# ItsyBitsy_Expander_v1_0.net
KiCad netlist of a schematic drawn in EAGLE
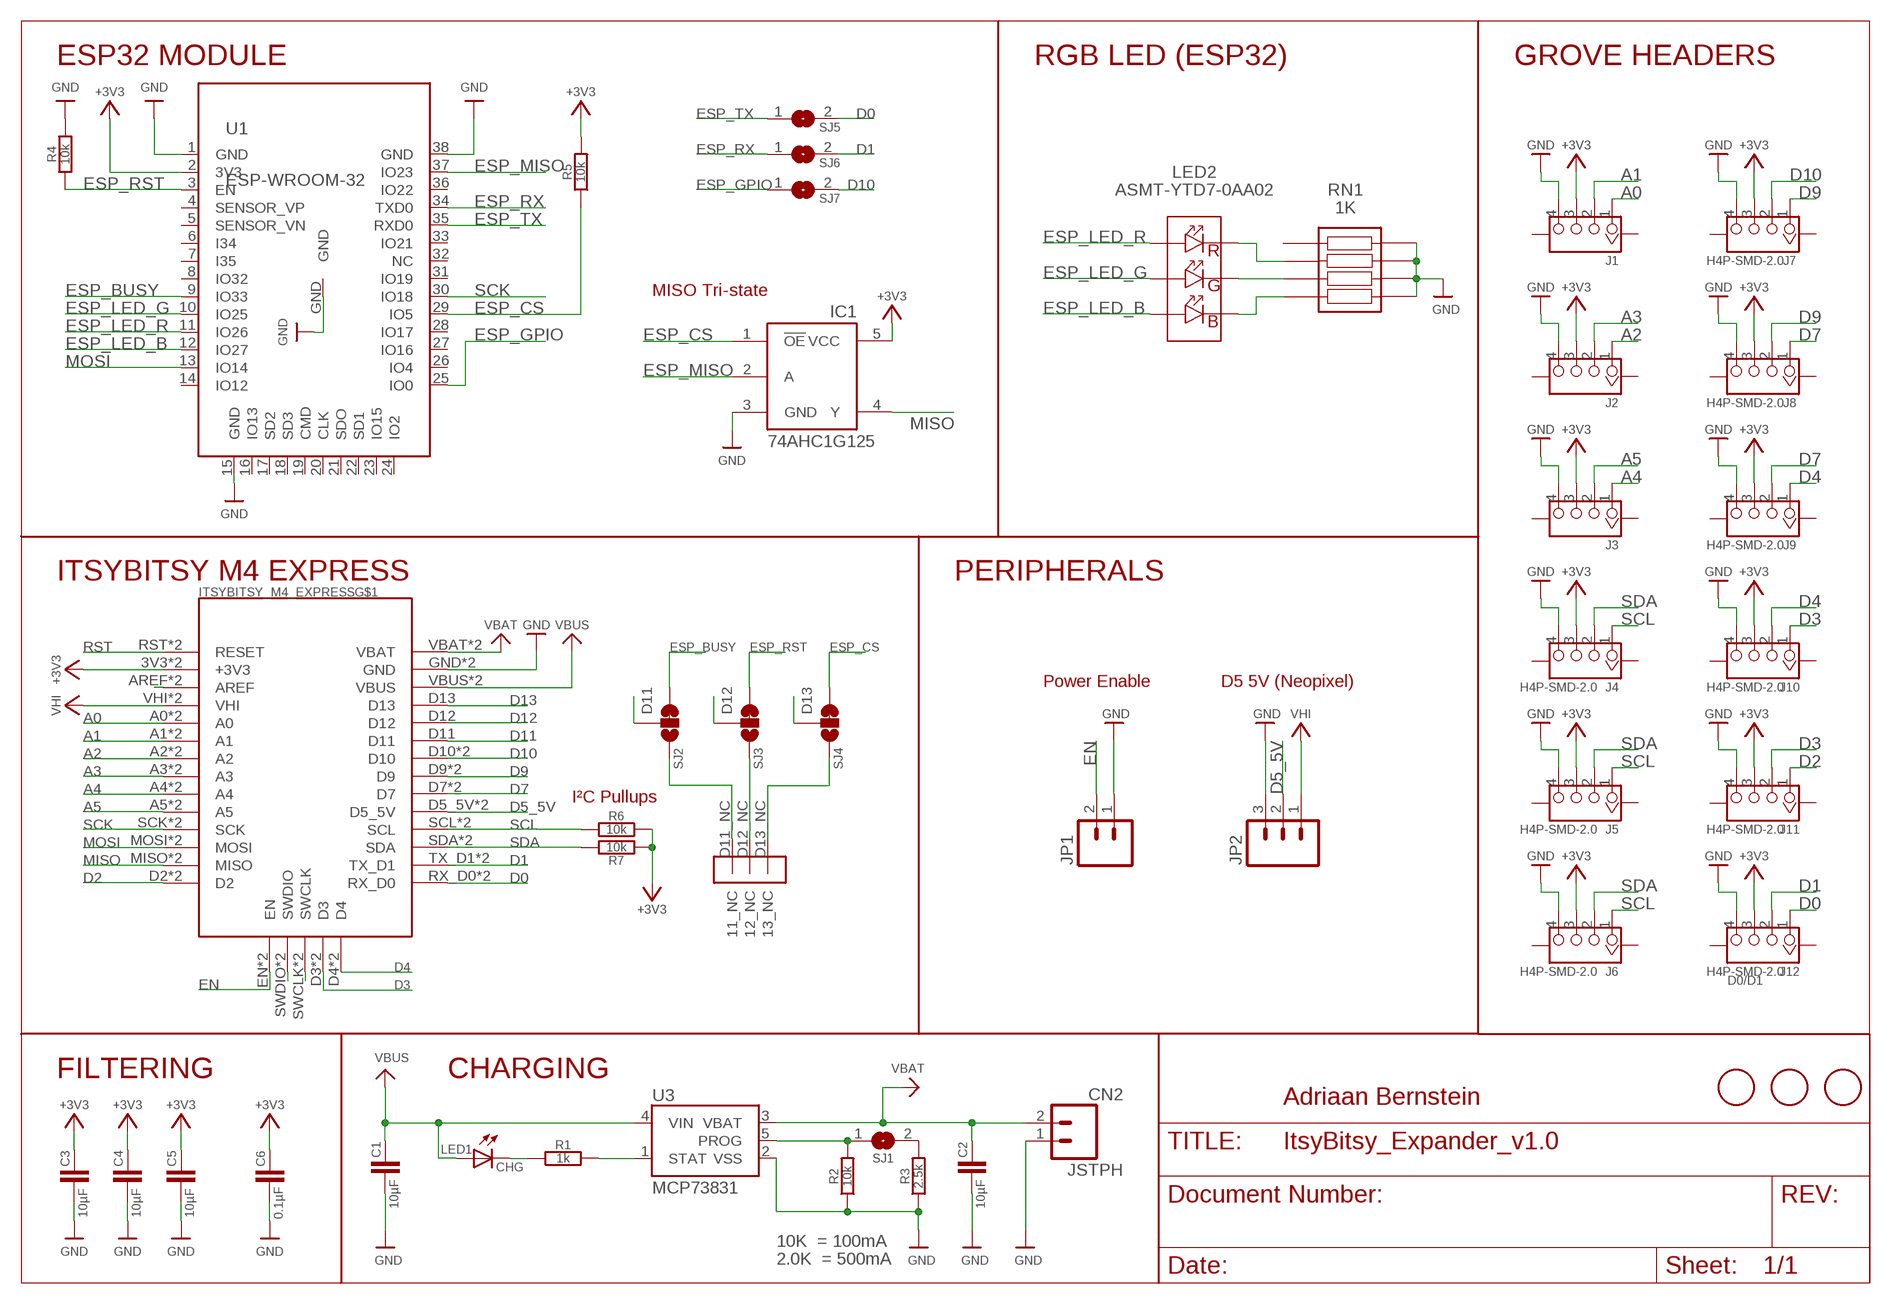
[diagram p0: schematic, sheet 1]

(export (version "E")
  (design (tool "Eeschema 10.0.6"))
  (components
    (comp (ref "C1")
      (value "10µF")
      (footprint "eagle-import:C0805")
      (libsource (lib "eagle-import") (part "C-EUC0805"))
    )
    (comp (ref "C2")
      (value "10µF")
      (footprint "eagle-import:C0805")
      (libsource (lib "eagle-import") (part "C-EUC0805"))
    )
    (comp (ref "C3")
      (value "10µF")
      (footprint "eagle-import:C0805")
      (libsource (lib "eagle-import") (part "C-EUC0805"))
    )
    (comp (ref "C4")
      (value "10µF")
      (footprint "eagle-import:C0805")
      (libsource (lib "eagle-import") (part "C-EUC0805"))
    )
    (comp (ref "C5")
      (value "10µF")
      (footprint "eagle-import:C0805")
      (libsource (lib "eagle-import") (part "C-EUC0805"))
    )
    (comp (ref "C6")
      (value "0.1µF")
      (footprint "eagle-import:C0603")
      (libsource (lib "eagle-import") (part "C-EUC0603"))
    )
    (comp (ref "CN2")
      (value "JSTPH")
      (footprint "eagle-import:JST-2-SMD")
      (libsource (lib "eagle-import") (part "M02-JST-2MM-SMT"))
    )
    (comp (ref "IC1")
      (value "74AHC1G125")
      (footprint "eagle-import:SOT23-5L")
      (libsource (lib "eagle-import") (part "74AHC1G125"))
    )
    (comp (ref "ITSYBITSY_M4_EXPRESS")
      (value "ITSYBITSY_M4_NC")
      (footprint "eagle-import:ITSYBITSY_M4_MIXED_DOUBLEHEADERS_ALL_NC")
      (libsource (lib "eagle-import") (part "ITSYBITSY_M4_NC"))
    )
    (comp (ref "J1")
      (value "H4P-SMD-2.0")
      (footprint "eagle-import:HW4-SMD-2.0")
      (libsource (lib "eagle-import") (part "GROVE-CONNECTOR-4PIN"))
    )
    (comp (ref "J2")
      (value "H4P-SMD-2.0")
      (footprint "eagle-import:HW4-SMD-2.0")
      (libsource (lib "eagle-import") (part "GROVE-CONNECTOR-4PIN"))
    )
    (comp (ref "J3")
      (value "H4P-SMD-2.0")
      (footprint "eagle-import:HW4-SMD-2.0")
      (libsource (lib "eagle-import") (part "GROVE-CONNECTOR-4PIN"))
    )
    (comp (ref "J4")
      (value "H4P-SMD-2.0")
      (footprint "eagle-import:HW4-SMD-2.0")
      (libsource (lib "eagle-import") (part "GROVE-CONNECTOR-4PIN"))
    )
    (comp (ref "J5")
      (value "H4P-SMD-2.0")
      (footprint "eagle-import:HW4-SMD-2.0")
      (libsource (lib "eagle-import") (part "GROVE-CONNECTOR-4PIN"))
    )
    (comp (ref "J6")
      (value "H4P-SMD-2.0")
      (footprint "eagle-import:HW4-SMD-2.0")
      (libsource (lib "eagle-import") (part "GROVE-CONNECTOR-4PIN"))
    )
    (comp (ref "J7")
      (value "H4P-SMD-2.0")
      (footprint "eagle-import:HW4-SMD-2.0")
      (libsource (lib "eagle-import") (part "GROVE-CONNECTOR-4PIN"))
    )
    (comp (ref "J8")
      (value "H4P-SMD-2.0")
      (footprint "eagle-import:HW4-SMD-2.0")
      (libsource (lib "eagle-import") (part "GROVE-CONNECTOR-4PIN"))
    )
    (comp (ref "J9")
      (value "H4P-SMD-2.0")
      (footprint "eagle-import:HW4-SMD-2.0")
      (libsource (lib "eagle-import") (part "GROVE-CONNECTOR-4PIN"))
    )
    (comp (ref "J10")
      (value "H4P-SMD-2.0")
      (footprint "eagle-import:HW4-SMD-2.0")
      (libsource (lib "eagle-import") (part "GROVE-CONNECTOR-4PIN"))
    )
    (comp (ref "J11")
      (value "H4P-SMD-2.0")
      (footprint "eagle-import:HW4-SMD-2.0")
      (libsource (lib "eagle-import") (part "GROVE-CONNECTOR-4PIN"))
    )
    (comp (ref "J12")
      (value "H4P-SMD-2.0")
      (footprint "eagle-import:HW4-SMD-2.0")
      (libsource (lib "eagle-import") (part "GROVE-CONNECTOR-4PIN"))
    )
    (comp (ref "JP1")
      (value "M02PTH")
      (footprint "eagle-import:1X02")
      (libsource (lib "eagle-import") (part "M02PTH"))
    )
    (comp (ref "JP2")
      (value "M03PTH")
      (footprint "eagle-import:1X03")
      (libsource (lib "eagle-import") (part "M03PTH"))
    )
    (comp (ref "LED1")
      (value "CHG")
      (footprint "eagle-import:CHIP-LED0603")
      (libsource (lib "eagle-import") (part "LEDCHIP-LED0603"))
    )
    (comp (ref "LED2")
      (value "ASMT-YTD7-0AA02")
      (footprint "eagle-import:ASMTYTD70AA02")
      (fields (field (name "MOUSER_PART_NUMBER") "630-ASMT-YTD7-0AA02"))
      (libsource (lib "eagle-import") (part "ASMT-YTD7-0AA02"))
    )
    (comp (ref "R1")
      (value "1k")
      (footprint "eagle-import:R0603")
      (libsource (lib "eagle-import") (part "R-EU_R0603"))
    )
    (comp (ref "R2")
      (value "10k")
      (footprint "eagle-import:R0603")
      (libsource (lib "eagle-import") (part "R-EU_R0603"))
    )
    (comp (ref "R3")
      (value "2.5k")
      (footprint "eagle-import:R0603")
      (libsource (lib "eagle-import") (part "R-EU_R0603"))
    )
    (comp (ref "R4")
      (value "10k")
      (footprint "eagle-import:R0603")
      (libsource (lib "eagle-import") (part "R-EU_R0603"))
    )
    (comp (ref "R5")
      (value "10k")
      (footprint "eagle-import:R0603")
      (libsource (lib "eagle-import") (part "R-EU_R0603"))
    )
    (comp (ref "R6")
      (value "10k")
      (footprint "eagle-import:R0603")
      (libsource (lib "eagle-import") (part "R-EU_R0603"))
    )
    (comp (ref "R7")
      (value "10k")
      (footprint "eagle-import:R0603")
      (libsource (lib "eagle-import") (part "R-EU_R0603"))
    )
    (comp (ref "RN1")
      (value "1K")
      (footprint "eagle-import:CAY1647R0F4LF")
      (fields
        (field (name "MANUFACTURER_PART_NUMBER") "CAY16-221J4AS")
        (field (name "MOUSER_PART_NUMBER") "652-CAY16-221J4AS")
      )
      (libsource (lib "eagle-import") (part "CAY16-221J4AS"))
    )
    (comp (ref "SJ1") (value "SJ") (footprint "eagle-import:SJ") (libsource (lib "eagle-import") (part "SJ")))
    (comp (ref "SJ5") (value "SJ") (footprint "eagle-import:SJ") (libsource (lib "eagle-import") (part "SJ")))
    (comp (ref "SJ6") (value "SJ") (footprint "eagle-import:SJ") (libsource (lib "eagle-import") (part "SJ")))
    (comp (ref "SJ7") (value "SJ") (footprint "eagle-import:SJ") (libsource (lib "eagle-import") (part "SJ")))
    (comp (ref "SJ_D11")
      (value "SJ2")
      (footprint "eagle-import:SJ_2WAY_CLOSED")
      (libsource (lib "eagle-import") (part "SJ_2WAY_CLOSED"))
    )
    (comp (ref "SJ_D12")
      (value "SJ3")
      (footprint "eagle-import:SJ_2WAY_CLOSED")
      (libsource (lib "eagle-import") (part "SJ_2WAY_CLOSED"))
    )
    (comp (ref "SJ_D13")
      (value "SJ4")
      (footprint "eagle-import:SJ_2WAY_CLOSED")
      (libsource (lib "eagle-import") (part "SJ_2WAY_CLOSED"))
    )
    (comp (ref "U$23")
      (value "FIDUCIAL")
      (footprint "eagle-import:FIDUCIAL_1MM")
      (libsource (lib "eagle-import") (part "FIDUCIAL"))
    )
    (comp (ref "U$35")
      (value "FIDUCIAL")
      (footprint "eagle-import:FIDUCIAL_1MM")
      (libsource (lib "eagle-import") (part "FIDUCIAL"))
    )
    (comp (ref "U$36")
      (value "FIDUCIAL")
      (footprint "eagle-import:FIDUCIAL_1MM")
      (libsource (lib "eagle-import") (part "FIDUCIAL"))
    )
    (comp (ref "U1")
      (value "ESP-WROOM-32")
      (footprint "eagle-import:ESP-WROOM-32")
      (libsource (lib "eagle-import") (part "ESP-WROOM-32"))
    )
    (comp (ref "U3")
      (value "MCP73831")
      (footprint "eagle-import:SOT23-5")
      (libsource (lib "eagle-import") (part "MCP73831"))
    )
  )
  (nets
    (net (code "1") (name "+3V3") (class "Default")
      (node (ref "C3") (pin "1") (pinfunction "1_1") (pintype "passive"))
      (node (ref "C4") (pin "1") (pinfunction "1_1") (pintype "passive"))
      (node (ref "C5") (pin "1") (pinfunction "1_1") (pintype "passive"))
      (node (ref "C6") (pin "1") (pinfunction "1_1") (pintype "passive"))
      (node (ref "IC1") (pin "5") (pinfunction "VCC_5") (pintype "power_in"))
      (node (ref "ITSYBITSY_M4_EXPRESS") (pin "3V3") (pinfunction "+3V3_3V3") (pintype "bidirectional"))
      (node (ref "ITSYBITSY_M4_EXPRESS") (pin "3V3_2") (pinfunction "+3V3_3V3_2") (pintype "bidirectional"))
      (node (ref "J1") (pin "3") (pinfunction "3_3") (pintype "bidirectional"))
      (node (ref "J10") (pin "3") (pinfunction "3_3") (pintype "bidirectional"))
      (node (ref "J11") (pin "3") (pinfunction "3_3") (pintype "bidirectional"))
      (node (ref "J12") (pin "3") (pinfunction "3_3") (pintype "bidirectional"))
      (node (ref "J2") (pin "3") (pinfunction "3_3") (pintype "bidirectional"))
      (node (ref "J3") (pin "3") (pinfunction "3_3") (pintype "bidirectional"))
      (node (ref "J4") (pin "3") (pinfunction "3_3") (pintype "bidirectional"))
      (node (ref "J5") (pin "3") (pinfunction "3_3") (pintype "bidirectional"))
      (node (ref "J6") (pin "3") (pinfunction "3_3") (pintype "bidirectional"))
      (node (ref "J7") (pin "3") (pinfunction "3_3") (pintype "bidirectional"))
      (node (ref "J8") (pin "3") (pinfunction "3_3") (pintype "bidirectional"))
      (node (ref "J9") (pin "3") (pinfunction "3_3") (pintype "bidirectional"))
      (node (ref "R5") (pin "2") (pinfunction "2_2") (pintype "passive"))
      (node (ref "R6") (pin "1") (pinfunction "1_1") (pintype "passive"))
      (node (ref "R7") (pin "1") (pinfunction "1_1") (pintype "passive"))
      (node (ref "U1") (pin "2") (pinfunction "3V3_2") (pintype "bidirectional"))
    )
    (net (code "2") (name "/A0") (class "Default")
      (node (ref "ITSYBITSY_M4_EXPRESS") (pin "A0") (pinfunction "A0_A0") (pintype "bidirectional"))
      (node (ref "ITSYBITSY_M4_EXPRESS") (pin "A0_2") (pinfunction "A0_A0_2") (pintype "bidirectional"))
      (node (ref "J1") (pin "1") (pinfunction "1_1") (pintype "bidirectional"))
    )
    (net (code "3") (name "/A1") (class "Default")
      (node (ref "ITSYBITSY_M4_EXPRESS") (pin "A1") (pinfunction "A1_A1") (pintype "bidirectional"))
      (node (ref "ITSYBITSY_M4_EXPRESS") (pin "A1_2") (pinfunction "A1_A1_2") (pintype "bidirectional"))
      (node (ref "J1") (pin "2") (pinfunction "2_2") (pintype "bidirectional"))
    )
    (net (code "4") (name "/A2") (class "Default")
      (node (ref "ITSYBITSY_M4_EXPRESS") (pin "A2") (pinfunction "A2_A2") (pintype "bidirectional"))
      (node (ref "ITSYBITSY_M4_EXPRESS") (pin "A2_2") (pinfunction "A2_A2_2") (pintype "bidirectional"))
      (node (ref "J2") (pin "1") (pinfunction "1_1") (pintype "bidirectional"))
    )
    (net (code "5") (name "/A3") (class "Default")
      (node (ref "ITSYBITSY_M4_EXPRESS") (pin "A3") (pinfunction "A3_A3") (pintype "bidirectional"))
      (node (ref "ITSYBITSY_M4_EXPRESS") (pin "A3_3") (pinfunction "A3_A3_3") (pintype "bidirectional"))
      (node (ref "J2") (pin "2") (pinfunction "2_2") (pintype "bidirectional"))
    )
    (net (code "6") (name "/A4") (class "Default")
      (node (ref "ITSYBITSY_M4_EXPRESS") (pin "A4") (pinfunction "A4_A4") (pintype "bidirectional"))
      (node (ref "ITSYBITSY_M4_EXPRESS") (pin "A4_2") (pinfunction "A4_A4_2") (pintype "bidirectional"))
      (node (ref "J3") (pin "1") (pinfunction "1_1") (pintype "bidirectional"))
    )
    (net (code "7") (name "/A5") (class "Default")
      (node (ref "ITSYBITSY_M4_EXPRESS") (pin "A5") (pinfunction "A5_A5") (pintype "bidirectional"))
      (node (ref "ITSYBITSY_M4_EXPRESS") (pin "A5_2") (pinfunction "A5_A5_2") (pintype "bidirectional"))
      (node (ref "J3") (pin "2") (pinfunction "2_2") (pintype "bidirectional"))
    )
    (net (code "8") (name "/D0") (class "Default")
      (node (ref "ITSYBITSY_M4_EXPRESS") (pin "RX_D0") (pinfunction "RX_D0_RX_D0") (pintype "bidirectional"))
      (node (ref "ITSYBITSY_M4_EXPRESS") (pin "RX_D0_2") (pinfunction "RX_D0_RX_D0_2") (pintype "bidirectional"))
      (node (ref "J12") (pin "1") (pinfunction "1_1") (pintype "bidirectional"))
      (node (ref "SJ5") (pin "2") (pinfunction "2_2") (pintype "passive"))
    )
    (net (code "9") (name "/D1") (class "Default")
      (node (ref "ITSYBITSY_M4_EXPRESS") (pin "TX_D1") (pinfunction "TX_D1_TX_D1") (pintype "bidirectional"))
      (node (ref "ITSYBITSY_M4_EXPRESS") (pin "TX_D1_2") (pinfunction "TX_D1_TX_D1_2") (pintype "bidirectional"))
      (node (ref "J12") (pin "2") (pinfunction "2_2") (pintype "bidirectional"))
      (node (ref "SJ6") (pin "2") (pinfunction "2_2") (pintype "passive"))
    )
    (net (code "10") (name "/D2") (class "Default")
      (node (ref "ITSYBITSY_M4_EXPRESS") (pin "D2") (pinfunction "D2_D2") (pintype "bidirectional"))
      (node (ref "ITSYBITSY_M4_EXPRESS") (pin "D2_2") (pinfunction "D2_D2_2") (pintype "bidirectional"))
      (node (ref "J11") (pin "1") (pinfunction "1_1") (pintype "bidirectional"))
    )
    (net (code "11") (name "/D3") (class "Default")
      (node (ref "ITSYBITSY_M4_EXPRESS") (pin "D3") (pinfunction "D3_D3") (pintype "bidirectional"))
      (node (ref "ITSYBITSY_M4_EXPRESS") (pin "D3_2") (pinfunction "D3_D3_2") (pintype "bidirectional"))
      (node (ref "J10") (pin "1") (pinfunction "1_1") (pintype "bidirectional"))
      (node (ref "J11") (pin "2") (pinfunction "2_2") (pintype "bidirectional"))
    )
    (net (code "12") (name "/D4") (class "Default")
      (node (ref "ITSYBITSY_M4_EXPRESS") (pin "D4") (pinfunction "D4_D4") (pintype "bidirectional"))
      (node (ref "ITSYBITSY_M4_EXPRESS") (pin "D4_2") (pinfunction "D4_D4_2") (pintype "bidirectional"))
      (node (ref "J10") (pin "2") (pinfunction "2_2") (pintype "bidirectional"))
      (node (ref "J9") (pin "1") (pinfunction "1_1") (pintype "bidirectional"))
    )
    (net (code "13") (name "/D5_5V") (class "Default")
      (node (ref "ITSYBITSY_M4_EXPRESS") (pin "D5_5V") (pinfunction "D5_5V_D5_5V") (pintype "bidirectional"))
      (node (ref "ITSYBITSY_M4_EXPRESS") (pin "D5_5V_2") (pinfunction "D5_5V_D5_5V_2") (pintype "bidirectional"))
      (node (ref "JP2") (pin "2") (pinfunction "2_2") (pintype "passive"))
    )
    (net (code "14") (name "/D7") (class "Default")
      (node (ref "ITSYBITSY_M4_EXPRESS") (pin "D7") (pinfunction "D7_D7") (pintype "bidirectional"))
      (node (ref "ITSYBITSY_M4_EXPRESS") (pin "D7_2") (pinfunction "D7_D7_2") (pintype "bidirectional"))
      (node (ref "J8") (pin "1") (pinfunction "1_1") (pintype "bidirectional"))
      (node (ref "J9") (pin "2") (pinfunction "2_2") (pintype "bidirectional"))
    )
    (net (code "15") (name "/D9") (class "Default")
      (node (ref "ITSYBITSY_M4_EXPRESS") (pin "D9") (pinfunction "D9_D9") (pintype "bidirectional"))
      (node (ref "ITSYBITSY_M4_EXPRESS") (pin "D9_2") (pinfunction "D9_D9_2") (pintype "bidirectional"))
      (node (ref "J7") (pin "1") (pinfunction "1_1") (pintype "bidirectional"))
      (node (ref "J8") (pin "2") (pinfunction "2_2") (pintype "bidirectional"))
    )
    (net (code "16") (name "/D10") (class "Default")
      (node (ref "ITSYBITSY_M4_EXPRESS") (pin "D10") (pinfunction "D10_D10") (pintype "bidirectional"))
      (node (ref "ITSYBITSY_M4_EXPRESS") (pin "D10_2") (pinfunction "D10_D10_2") (pintype "bidirectional"))
      (node (ref "J7") (pin "2") (pinfunction "2_2") (pintype "bidirectional"))
      (node (ref "SJ7") (pin "2") (pinfunction "2_2") (pintype "passive"))
    )
    (net (code "17") (name "/D11") (class "Default")
      (node (ref "ITSYBITSY_M4_EXPRESS") (pin "D11") (pinfunction "D11_D11") (pintype "bidirectional"))
      (node (ref "SJ_D11") (pin "2") (pinfunction "2_2") (pintype "passive"))
    )
    (net (code "18") (name "/D12") (class "Default")
      (node (ref "ITSYBITSY_M4_EXPRESS") (pin "D12") (pinfunction "D12_D12") (pintype "bidirectional"))
      (node (ref "SJ_D12") (pin "2") (pinfunction "2_2") (pintype "passive"))
    )
    (net (code "19") (name "/D13") (class "Default")
      (node (ref "ITSYBITSY_M4_EXPRESS") (pin "D13") (pinfunction "D13_D13") (pintype "bidirectional"))
      (node (ref "SJ_D13") (pin "2") (pinfunction "2_2") (pintype "passive"))
    )
    (net (code "20") (name "/EN") (class "Default")
      (node (ref "ITSYBITSY_M4_EXPRESS") (pin "EN") (pinfunction "EN_EN") (pintype "bidirectional"))
      (node (ref "ITSYBITSY_M4_EXPRESS") (pin "EN_2") (pinfunction "EN_EN_2") (pintype "bidirectional"))
      (node (ref "JP1") (pin "2") (pinfunction "2_2") (pintype "passive"))
    )
    (net (code "21") (name "/ESP_BUSY") (class "Default")
      (node (ref "SJ_D11") (pin "1") (pinfunction "1_1") (pintype "passive"))
      (node (ref "U1") (pin "9") (pinfunction "IO33_9") (pintype "bidirectional"))
    )
    (net (code "22") (name "/ESP_CS") (class "Default")
      (node (ref "IC1") (pin "1") (pinfunction "~{OE}_1") (pintype "input"))
      (node (ref "R5") (pin "1") (pinfunction "1_1") (pintype "passive"))
      (node (ref "SJ_D13") (pin "1") (pinfunction "1_1") (pintype "passive"))
      (node (ref "U1") (pin "29") (pinfunction "IO5_29") (pintype "bidirectional"))
    )
    (net (code "23") (name "/ESP_GPIO") (class "Default")
      (node (ref "SJ7") (pin "1") (pinfunction "1_1") (pintype "passive"))
      (node (ref "U1") (pin "25") (pinfunction "IO0_25") (pintype "bidirectional"))
    )
    (net (code "24") (name "/ESP_LED_B") (class "Default")
      (node (ref "LED2") (pin "6") (pinfunction "A_BLUE_6") (pintype "bidirectional"))
      (node (ref "U1") (pin "12") (pinfunction "IO27_12") (pintype "bidirectional"))
    )
    (net (code "25") (name "/ESP_LED_G") (class "Default")
      (node (ref "LED2") (pin "5") (pinfunction "A_GREEN_5") (pintype "bidirectional"))
      (node (ref "U1") (pin "10") (pinfunction "IO25_10") (pintype "bidirectional"))
    )
    (net (code "26") (name "/ESP_LED_R") (class "Default")
      (node (ref "LED2") (pin "4") (pinfunction "A_RED_4") (pintype "bidirectional"))
      (node (ref "U1") (pin "11") (pinfunction "IO26_11") (pintype "bidirectional"))
    )
    (net (code "27") (name "/ESP_MISO") (class "Default")
      (node (ref "IC1") (pin "2") (pinfunction "A_2") (pintype "input"))
      (node (ref "U1") (pin "37") (pinfunction "IO23_37") (pintype "bidirectional"))
    )
    (net (code "28") (name "/ESP_RST") (class "Default")
      (node (ref "R4") (pin "1") (pinfunction "1_1") (pintype "passive"))
      (node (ref "SJ_D12") (pin "1") (pinfunction "1_1") (pintype "passive"))
      (node (ref "U1") (pin "3") (pinfunction "EN_3") (pintype "bidirectional"))
    )
    (net (code "29") (name "/ESP_RX") (class "Default")
      (node (ref "SJ6") (pin "1") (pinfunction "1_1") (pintype "passive"))
      (node (ref "U1") (pin "34") (pinfunction "TXD0_34") (pintype "bidirectional"))
    )
    (net (code "30") (name "/ESP_TX") (class "Default")
      (node (ref "SJ5") (pin "1") (pinfunction "1_1") (pintype "passive"))
      (node (ref "U1") (pin "35") (pinfunction "RXD0_35") (pintype "bidirectional"))
    )
    (net (code "31") (name "/MISO") (class "Default")
      (node (ref "IC1") (pin "4") (pinfunction "Y_4") (pintype "output"))
      (node (ref "ITSYBITSY_M4_EXPRESS") (pin "MISO") (pinfunction "MISO_MISO") (pintype "bidirectional"))
      (node (ref "ITSYBITSY_M4_EXPRESS") (pin "MISO_2") (pinfunction "MISO_MISO_2") (pintype "bidirectional"))
    )
    (net (code "32") (name "/MOSI") (class "Default")
      (node (ref "ITSYBITSY_M4_EXPRESS") (pin "MOSI") (pinfunction "MOSI_MOSI") (pintype "bidirectional"))
      (node (ref "ITSYBITSY_M4_EXPRESS") (pin "MOSI_2") (pinfunction "MOSI_MOSI_2") (pintype "bidirectional"))
      (node (ref "U1") (pin "13") (pinfunction "IO14_13") (pintype "bidirectional"))
    )
    (net (code "33") (name "/RST") (class "Default")
      (node (ref "ITSYBITSY_M4_EXPRESS") (pin "RST") (pinfunction "RESET_RST") (pintype "bidirectional"))
      (node (ref "ITSYBITSY_M4_EXPRESS") (pin "RST_2") (pinfunction "RESET_RST_2") (pintype "bidirectional"))
    )
    (net (code "34") (name "/SCK") (class "Default")
      (node (ref "ITSYBITSY_M4_EXPRESS") (pin "SCK") (pinfunction "SCK_SCK") (pintype "bidirectional"))
      (node (ref "ITSYBITSY_M4_EXPRESS") (pin "SCK_2") (pinfunction "SCK_SCK_2") (pintype "bidirectional"))
      (node (ref "U1") (pin "30") (pinfunction "IO18_30") (pintype "bidirectional"))
    )
    (net (code "35") (name "/SCL") (class "Default")
      (node (ref "ITSYBITSY_M4_EXPRESS") (pin "SCL") (pinfunction "SCL_SCL") (pintype "bidirectional"))
      (node (ref "ITSYBITSY_M4_EXPRESS") (pin "SCL_2") (pinfunction "SCL_SCL_2") (pintype "bidirectional"))
      (node (ref "J4") (pin "1") (pinfunction "1_1") (pintype "bidirectional"))
      (node (ref "J5") (pin "1") (pinfunction "1_1") (pintype "bidirectional"))
      (node (ref "J6") (pin "1") (pinfunction "1_1") (pintype "bidirectional"))
      (node (ref "R6") (pin "2") (pinfunction "2_2") (pintype "passive"))
    )
    (net (code "36") (name "/SDA") (class "Default")
      (node (ref "ITSYBITSY_M4_EXPRESS") (pin "SDA") (pinfunction "SDA_SDA") (pintype "bidirectional"))
      (node (ref "ITSYBITSY_M4_EXPRESS") (pin "SDA_2") (pinfunction "SDA_SDA_2") (pintype "bidirectional"))
      (node (ref "J4") (pin "2") (pinfunction "2_2") (pintype "bidirectional"))
      (node (ref "J5") (pin "2") (pinfunction "2_2") (pintype "bidirectional"))
      (node (ref "J6") (pin "2") (pinfunction "2_2") (pintype "bidirectional"))
      (node (ref "R7") (pin "2") (pinfunction "2_2") (pintype "passive"))
    )
    (net (code "37") (name "GND") (class "Default")
      (node (ref "C1") (pin "2") (pinfunction "2_2") (pintype "passive"))
      (node (ref "C2") (pin "2") (pinfunction "2_2") (pintype "passive"))
      (node (ref "C3") (pin "2") (pinfunction "2_2") (pintype "passive"))
      (node (ref "C4") (pin "2") (pinfunction "2_2") (pintype "passive"))
      (node (ref "C5") (pin "2") (pinfunction "2_2") (pintype "passive"))
      (node (ref "C6") (pin "2") (pinfunction "2_2") (pintype "passive"))
      (node (ref "CN2") (pin "1") (pinfunction "1_1") (pintype "passive"))
      (node (ref "IC1") (pin "3") (pinfunction "GND_3") (pintype "power_in"))
      (node (ref "ITSYBITSY_M4_EXPRESS") (pin "GND") (pinfunction "GND_GND") (pintype "bidirectional"))
      (node (ref "ITSYBITSY_M4_EXPRESS") (pin "GND_2") (pinfunction "GND_GND_2") (pintype "bidirectional"))
      (node (ref "J1") (pin "4") (pinfunction "4_4") (pintype "bidirectional"))
      (node (ref "J10") (pin "4") (pinfunction "4_4") (pintype "bidirectional"))
      (node (ref "J11") (pin "4") (pinfunction "4_4") (pintype "bidirectional"))
      (node (ref "J12") (pin "4") (pinfunction "4_4") (pintype "bidirectional"))
      (node (ref "J2") (pin "4") (pinfunction "4_4") (pintype "bidirectional"))
      (node (ref "J3") (pin "4") (pinfunction "4_4") (pintype "bidirectional"))
      (node (ref "J4") (pin "4") (pinfunction "4_4") (pintype "bidirectional"))
      (node (ref "J5") (pin "4") (pinfunction "4_4") (pintype "bidirectional"))
      (node (ref "J6") (pin "4") (pinfunction "4_4") (pintype "bidirectional"))
      (node (ref "J7") (pin "4") (pinfunction "4_4") (pintype "bidirectional"))
      (node (ref "J8") (pin "4") (pinfunction "4_4") (pintype "bidirectional"))
      (node (ref "J9") (pin "4") (pinfunction "4_4") (pintype "bidirectional"))
      (node (ref "JP1") (pin "1") (pinfunction "1_1") (pintype "passive"))
      (node (ref "JP2") (pin "3") (pinfunction "3_3") (pintype "passive"))
      (node (ref "R2") (pin "1") (pinfunction "1_1") (pintype "passive"))
      (node (ref "R3") (pin "1") (pinfunction "1_1") (pintype "passive"))
      (node (ref "R4") (pin "2") (pinfunction "2_2") (pintype "passive"))
      (node (ref "RN1") (pin "5") (pinfunction "R4_2_5") (pintype "bidirectional"))
      (node (ref "RN1") (pin "6") (pinfunction "R3_2_6") (pintype "bidirectional"))
      (node (ref "RN1") (pin "7") (pinfunction "R2_2_7") (pintype "bidirectional"))
      (node (ref "RN1") (pin "8") (pinfunction "R1_2_8") (pintype "bidirectional"))
      (node (ref "U1") (pin "1") (pinfunction "GND_1") (pintype "bidirectional"))
      (node (ref "U1") (pin "15") (pinfunction "GND_15") (pintype "bidirectional"))
      (node (ref "U1") (pin "38") (pinfunction "GND_38") (pintype "bidirectional"))
      (node (ref "U1") (pin "GND") (pinfunction "GND_GND") (pintype "bidirectional"))
      (node (ref "U3") (pin "2") (pinfunction "VSS_2") (pintype "power_in"))
    )
    (net (code "38") (name "Net-(ITSYBITSY_M4_EXPRESS-PadAREF)") (class "Default")
      (node (ref "ITSYBITSY_M4_EXPRESS") (pin "AREF") (pinfunction "AREF_AREF") (pintype "bidirectional"))
      (node (ref "ITSYBITSY_M4_EXPRESS") (pin "AREF_2") (pinfunction "AREF_AREF_2") (pintype "bidirectional"))
    )
    (net (code "39") (name "Net-(ITSYBITSY_M4_EXPRESS-PadSWCLK)") (class "Default")
      (node (ref "ITSYBITSY_M4_EXPRESS") (pin "SWCLK") (pinfunction "SWCLK_SWCLK") (pintype "bidirectional"))
      (node (ref "ITSYBITSY_M4_EXPRESS") (pin "SWCLK_2") (pinfunction "SWCLK_SWCLK_2") (pintype "bidirectional"))
    )
    (net (code "40") (name "Net-(ITSYBITSY_M4_EXPRESS-PadSWDIO)") (class "Default")
      (node (ref "ITSYBITSY_M4_EXPRESS") (pin "SWDIO") (pinfunction "SWDIO_SWDIO") (pintype "bidirectional"))
      (node (ref "ITSYBITSY_M4_EXPRESS") (pin "SWDIO_2") (pinfunction "SWDIO_SWDIO_2") (pintype "bidirectional"))
    )
    (net (code "41") (name "Net-(ITSYBITSY_M4_EXPRESSB-11_NC)") (class "Default")
      (node (ref "ITSYBITSY_M4_EXPRESS") (pin "D11_NC") (pinfunction "11_NC_D11_NC") (pintype "bidirectional"))
      (node (ref "SJ_D11") (pin "3") (pinfunction "3_3") (pintype "passive"))
    )
    (net (code "42") (name "Net-(ITSYBITSY_M4_EXPRESSB-12_NC)") (class "Default")
      (node (ref "ITSYBITSY_M4_EXPRESS") (pin "D12_NC") (pinfunction "12_NC_D12_NC") (pintype "bidirectional"))
      (node (ref "SJ_D12") (pin "3") (pinfunction "3_3") (pintype "passive"))
    )
    (net (code "43") (name "Net-(ITSYBITSY_M4_EXPRESSB-13_NC)") (class "Default")
      (node (ref "ITSYBITSY_M4_EXPRESS") (pin "D13_NC") (pinfunction "13_NC_D13_NC") (pintype "bidirectional"))
      (node (ref "SJ_D13") (pin "3") (pinfunction "3_3") (pintype "passive"))
    )
    (net (code "44") (name "Net-(LED1-PadC)") (class "Default")
      (node (ref "LED1") (pin "C") (pinfunction "C_C") (pintype "passive"))
      (node (ref "R1") (pin "1") (pinfunction "1_1") (pintype "passive"))
    )
    (net (code "45") (name "Net-(LED2-K_BLUE)") (class "Default")
      (node (ref "LED2") (pin "1") (pinfunction "K_BLUE_1") (pintype "bidirectional"))
      (node (ref "RN1") (pin "4") (pinfunction "R4_1_4") (pintype "bidirectional"))
    )
    (net (code "46") (name "Net-(LED2-K_GREEN)") (class "Default")
      (node (ref "LED2") (pin "2") (pinfunction "K_GREEN_2") (pintype "bidirectional"))
      (node (ref "RN1") (pin "3") (pinfunction "R3_1_3") (pintype "bidirectional"))
    )
    (net (code "47") (name "Net-(LED2-K_RED)") (class "Default")
      (node (ref "LED2") (pin "3") (pinfunction "K_RED_3") (pintype "bidirectional"))
      (node (ref "RN1") (pin "2") (pinfunction "R2_1_2") (pintype "bidirectional"))
    )
    (net (code "48") (name "Net-(R3-Pad2)") (class "Default")
      (node (ref "R3") (pin "2") (pinfunction "2_2") (pintype "passive"))
      (node (ref "SJ1") (pin "2") (pinfunction "2_2") (pintype "passive"))
    )
    (net (code "49") (name "Net-(U3-PROG)") (class "Default")
      (node (ref "R2") (pin "2") (pinfunction "2_2") (pintype "passive"))
      (node (ref "SJ1") (pin "1") (pinfunction "1_1") (pintype "passive"))
      (node (ref "U3") (pin "5") (pinfunction "PROG_5") (pintype "input"))
    )
    (net (code "50") (name "Net-(U3-STAT)") (class "Default")
      (node (ref "R1") (pin "2") (pinfunction "2_2") (pintype "passive"))
      (node (ref "U3") (pin "1") (pinfunction "STAT_1") (pintype "output"))
    )
    (net (code "51") (name "VBAT") (class "Default")
      (node (ref "C2") (pin "1") (pinfunction "1_1") (pintype "passive"))
      (node (ref "CN2") (pin "2") (pinfunction "2_2") (pintype "passive"))
      (node (ref "ITSYBITSY_M4_EXPRESS") (pin "VBAT") (pinfunction "VBAT_VBAT") (pintype "bidirectional"))
      (node (ref "ITSYBITSY_M4_EXPRESS") (pin "VBAT_2") (pinfunction "VBAT_VBAT_2") (pintype "bidirectional"))
      (node (ref "U3") (pin "3") (pinfunction "VBAT_3") (pintype "power_in"))
    )
    (net (code "52") (name "VBUS") (class "Default")
      (node (ref "C1") (pin "1") (pinfunction "1_1") (pintype "passive"))
      (node (ref "ITSYBITSY_M4_EXPRESS") (pin "VBUS") (pinfunction "VBUS_VBUS") (pintype "bidirectional"))
      (node (ref "ITSYBITSY_M4_EXPRESS") (pin "VBUS_2") (pinfunction "VBUS_VBUS_2") (pintype "bidirectional"))
      (node (ref "LED1") (pin "A") (pinfunction "A_A") (pintype "passive"))
      (node (ref "U3") (pin "4") (pinfunction "VIN_4") (pintype "power_in"))
    )
    (net (code "53") (name "VHI") (class "Default")
      (node (ref "ITSYBITSY_M4_EXPRESS") (pin "VHI") (pinfunction "VHI_VHI") (pintype "bidirectional"))
      (node (ref "ITSYBITSY_M4_EXPRESS") (pin "VHI_2") (pinfunction "VHI_VHI_2") (pintype "bidirectional"))
      (node (ref "JP2") (pin "1") (pinfunction "1_1") (pintype "passive"))
    )
    (net (code "54") (name "unconnected-(J1-PadSS1)") (class "Default")
      (node (ref "J1") (pin "SS1") (pinfunction "SS1_SS1") (pintype "bidirectional"))
    )
    (net (code "55") (name "unconnected-(J1-PadSS2)") (class "Default")
      (node (ref "J1") (pin "SS2") (pinfunction "SS2_SS2") (pintype "bidirectional"))
    )
    (net (code "56") (name "unconnected-(J2-PadSS1)") (class "Default")
      (node (ref "J2") (pin "SS1") (pinfunction "SS1_SS1") (pintype "bidirectional"))
    )
    (net (code "57") (name "unconnected-(J2-PadSS2)") (class "Default")
      (node (ref "J2") (pin "SS2") (pinfunction "SS2_SS2") (pintype "bidirectional"))
    )
    (net (code "58") (name "unconnected-(J3-PadSS1)") (class "Default")
      (node (ref "J3") (pin "SS1") (pinfunction "SS1_SS1") (pintype "bidirectional"))
    )
    (net (code "59") (name "unconnected-(J3-PadSS2)") (class "Default")
      (node (ref "J3") (pin "SS2") (pinfunction "SS2_SS2") (pintype "bidirectional"))
    )
    (net (code "60") (name "unconnected-(J4-PadSS1)") (class "Default")
      (node (ref "J4") (pin "SS1") (pinfunction "SS1_SS1") (pintype "bidirectional"))
    )
    (net (code "61") (name "unconnected-(J4-PadSS2)") (class "Default")
      (node (ref "J4") (pin "SS2") (pinfunction "SS2_SS2") (pintype "bidirectional"))
    )
    (net (code "62") (name "unconnected-(J5-PadSS1)") (class "Default")
      (node (ref "J5") (pin "SS1") (pinfunction "SS1_SS1") (pintype "bidirectional"))
    )
    (net (code "63") (name "unconnected-(J5-PadSS2)") (class "Default")
      (node (ref "J5") (pin "SS2") (pinfunction "SS2_SS2") (pintype "bidirectional"))
    )
    (net (code "64") (name "unconnected-(J6-PadSS1)") (class "Default")
      (node (ref "J6") (pin "SS1") (pinfunction "SS1_SS1") (pintype "bidirectional"))
    )
    (net (code "65") (name "unconnected-(J6-PadSS2)") (class "Default")
      (node (ref "J6") (pin "SS2") (pinfunction "SS2_SS2") (pintype "bidirectional"))
    )
    (net (code "66") (name "unconnected-(J7-PadSS1)") (class "Default")
      (node (ref "J7") (pin "SS1") (pinfunction "SS1_SS1") (pintype "bidirectional"))
    )
    (net (code "67") (name "unconnected-(J7-PadSS2)") (class "Default")
      (node (ref "J7") (pin "SS2") (pinfunction "SS2_SS2") (pintype "bidirectional"))
    )
    (net (code "68") (name "unconnected-(J8-PadSS1)") (class "Default")
      (node (ref "J8") (pin "SS1") (pinfunction "SS1_SS1") (pintype "bidirectional"))
    )
    (net (code "69") (name "unconnected-(J8-PadSS2)") (class "Default")
      (node (ref "J8") (pin "SS2") (pinfunction "SS2_SS2") (pintype "bidirectional"))
    )
    (net (code "70") (name "unconnected-(J9-PadSS1)") (class "Default")
      (node (ref "J9") (pin "SS1") (pinfunction "SS1_SS1") (pintype "bidirectional"))
    )
    (net (code "71") (name "unconnected-(J9-PadSS2)") (class "Default")
      (node (ref "J9") (pin "SS2") (pinfunction "SS2_SS2") (pintype "bidirectional"))
    )
    (net (code "72") (name "unconnected-(J10-PadSS1)") (class "Default")
      (node (ref "J10") (pin "SS1") (pinfunction "SS1_SS1") (pintype "bidirectional"))
    )
    (net (code "73") (name "unconnected-(J10-PadSS2)") (class "Default")
      (node (ref "J10") (pin "SS2") (pinfunction "SS2_SS2") (pintype "bidirectional"))
    )
    (net (code "74") (name "unconnected-(J11-PadSS1)") (class "Default")
      (node (ref "J11") (pin "SS1") (pinfunction "SS1_SS1") (pintype "bidirectional"))
    )
    (net (code "75") (name "unconnected-(J11-PadSS2)") (class "Default")
      (node (ref "J11") (pin "SS2") (pinfunction "SS2_SS2") (pintype "bidirectional"))
    )
    (net (code "76") (name "unconnected-(J12-PadSS1)") (class "Default")
      (node (ref "J12") (pin "SS1") (pinfunction "SS1_SS1") (pintype "bidirectional"))
    )
    (net (code "77") (name "unconnected-(J12-PadSS2)") (class "Default")
      (node (ref "J12") (pin "SS2") (pinfunction "SS2_SS2") (pintype "bidirectional"))
    )
    (net (code "78") (name "unconnected-(RN1-R1_1-Pad1)") (class "Default")
      (node (ref "RN1") (pin "1") (pinfunction "R1_1_1") (pintype "bidirectional"))
    )
    (net (code "79") (name "unconnected-(U1-CLK-Pad20)") (class "Default")
      (node (ref "U1") (pin "20") (pinfunction "CLK_20") (pintype "bidirectional"))
    )
    (net (code "80") (name "unconnected-(U1-CMD-Pad19)") (class "Default")
      (node (ref "U1") (pin "19") (pinfunction "CMD_19") (pintype "bidirectional"))
    )
    (net (code "81") (name "unconnected-(U1-I34-Pad6)") (class "Default")
      (node (ref "U1") (pin "6") (pinfunction "I34_6") (pintype "input"))
    )
    (net (code "82") (name "unconnected-(U1-I35-Pad7)") (class "Default")
      (node (ref "U1") (pin "7") (pinfunction "I35_7") (pintype "input"))
    )
    (net (code "83") (name "unconnected-(U1-IO2-Pad24)") (class "Default")
      (node (ref "U1") (pin "24") (pinfunction "IO2_24") (pintype "bidirectional"))
    )
    (net (code "84") (name "unconnected-(U1-IO4-Pad26)") (class "Default")
      (node (ref "U1") (pin "26") (pinfunction "IO4_26") (pintype "bidirectional"))
    )
    (net (code "85") (name "unconnected-(U1-IO12-Pad14)") (class "Default")
      (node (ref "U1") (pin "14") (pinfunction "IO12_14") (pintype "bidirectional"))
    )
    (net (code "86") (name "unconnected-(U1-IO13-Pad16)") (class "Default")
      (node (ref "U1") (pin "16") (pinfunction "IO13_16") (pintype "bidirectional"))
    )
    (net (code "87") (name "unconnected-(U1-IO15-Pad23)") (class "Default")
      (node (ref "U1") (pin "23") (pinfunction "IO15_23") (pintype "bidirectional"))
    )
    (net (code "88") (name "unconnected-(U1-IO16-Pad27)") (class "Default")
      (node (ref "U1") (pin "27") (pinfunction "IO16_27") (pintype "bidirectional"))
    )
    (net (code "89") (name "unconnected-(U1-IO17-Pad28)") (class "Default")
      (node (ref "U1") (pin "28") (pinfunction "IO17_28") (pintype "bidirectional"))
    )
    (net (code "90") (name "unconnected-(U1-IO19-Pad31)") (class "Default")
      (node (ref "U1") (pin "31") (pinfunction "IO19_31") (pintype "bidirectional"))
    )
    (net (code "91") (name "unconnected-(U1-IO21-Pad33)") (class "Default")
      (node (ref "U1") (pin "33") (pinfunction "IO21_33") (pintype "bidirectional"))
    )
    (net (code "92") (name "unconnected-(U1-IO22-Pad36)") (class "Default")
      (node (ref "U1") (pin "36") (pinfunction "IO22_36") (pintype "bidirectional"))
    )
    (net (code "93") (name "unconnected-(U1-IO32-Pad8)") (class "Default")
      (node (ref "U1") (pin "8") (pinfunction "IO32_8") (pintype "bidirectional"))
    )
    (net (code "94") (name "unconnected-(U1-NC-Pad32)") (class "Default")
      (node (ref "U1") (pin "32") (pinfunction "NC_32") (pintype "bidirectional"))
    )
    (net (code "95") (name "unconnected-(U1-SD1-Pad22)") (class "Default")
      (node (ref "U1") (pin "22") (pinfunction "SD1_22") (pintype "bidirectional"))
    )
    (net (code "96") (name "unconnected-(U1-SD2-Pad17)") (class "Default")
      (node (ref "U1") (pin "17") (pinfunction "SD2_17") (pintype "bidirectional"))
    )
    (net (code "97") (name "unconnected-(U1-SD3-Pad18)") (class "Default")
      (node (ref "U1") (pin "18") (pinfunction "SD3_18") (pintype "bidirectional"))
    )
    (net (code "98") (name "unconnected-(U1-SDO-Pad21)") (class "Default")
      (node (ref "U1") (pin "21") (pinfunction "SDO_21") (pintype "bidirectional"))
    )
    (net (code "99") (name "unconnected-(U1-SENSOR_VN-Pad5)") (class "Default")
      (node (ref "U1") (pin "5") (pinfunction "SENSOR_VN_5") (pintype "input"))
    )
    (net (code "100") (name "unconnected-(U1-SENSOR_VP-Pad4)") (class "Default")
      (node (ref "U1") (pin "4") (pinfunction "SENSOR_VP_4") (pintype "input"))
    )
  )
)
